# ftdi_rs232_bsl.net
KiCad netlist of a schematic drawn in EAGLE
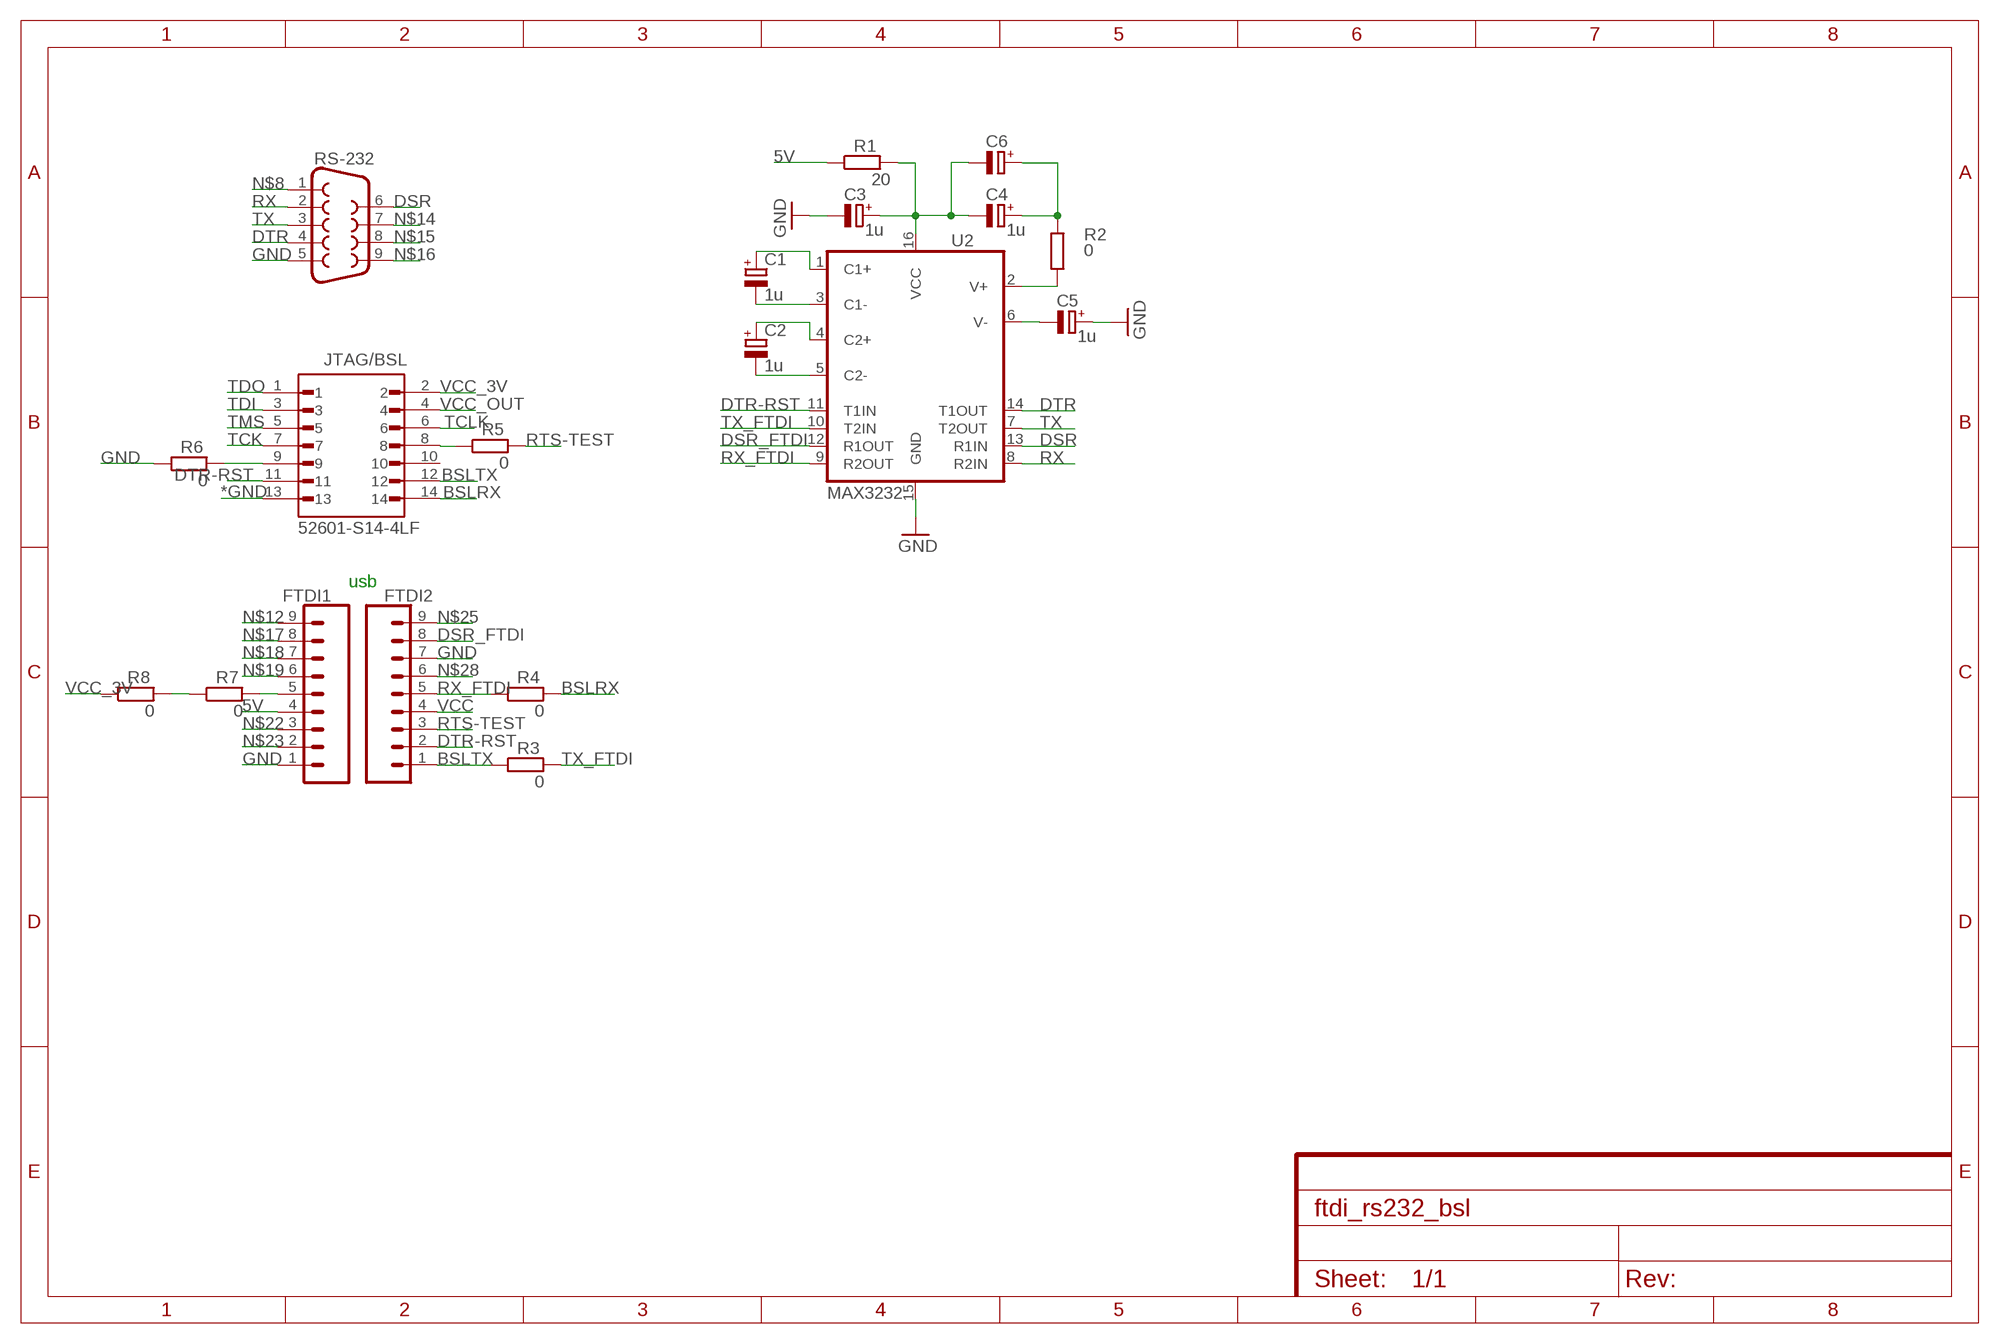
[diagram p0: schematic, sheet 1]

(export (version "E")
  (design (tool "Eeschema 10.0.6"))
  (components
    (comp (ref "C1")
      (value "1u")
      (footprint "eagle-import:B_3528-21W")
      (libsource (lib "eagle-import") (part "CPOL-EUB/3528-21W"))
    )
    (comp (ref "C2")
      (value "1u")
      (footprint "eagle-import:B_3528-21W")
      (libsource (lib "eagle-import") (part "CPOL-EUB/3528-21W"))
    )
    (comp (ref "C3")
      (value "1u")
      (footprint "eagle-import:B_3528-21W")
      (libsource (lib "eagle-import") (part "CPOL-EUB/3528-21W"))
    )
    (comp (ref "C4")
      (value "1u")
      (footprint "eagle-import:B_3528-21W")
      (libsource (lib "eagle-import") (part "CPOL-EUB/3528-21W"))
    )
    (comp (ref "C5")
      (value "1u")
      (footprint "eagle-import:B_3528-21W")
      (libsource (lib "eagle-import") (part "CPOL-EUB/3528-21W"))
    )
    (comp (ref "C6")
      (value "CPOL-EUB/3528-21W")
      (footprint "eagle-import:B_3528-21W")
      (libsource (lib "eagle-import") (part "CPOL-EUB/3528-21W"))
    )
    (comp (ref "FTDI1")
      (value "CONN_09NO_SILK")
      (footprint "eagle-import:1X09_NO_SILK")
      (libsource (lib "eagle-import") (part "CONN_09NO_SILK"))
    )
    (comp (ref "FTDI2")
      (value "CONN_09NO_SILK")
      (footprint "eagle-import:1X09_NO_SILK")
      (libsource (lib "eagle-import") (part "CONN_09NO_SILK"))
    )
    (comp (ref "JTAG/BSL")
      (value "52601-S14-4LF")
      (footprint "eagle-import:AMPHENOL_52601-S14-4LF")
      (fields (field (name "MF") "Amphenol ICC (FCI)"))
      (libsource (lib "eagle-import") (part "52601-S14-4LF"))
    )
    (comp (ref "R1")
      (value "20")
      (footprint "eagle-import:R1206")
      (libsource (lib "eagle-import") (part "R-EU_R1206"))
    )
    (comp (ref "R2")
      (value "0")
      (footprint "eagle-import:R1206")
      (libsource (lib "eagle-import") (part "R-EU_R1206"))
    )
    (comp (ref "R3")
      (value "0")
      (footprint "eagle-import:R1206")
      (libsource (lib "eagle-import") (part "R-EU_R1206"))
    )
    (comp (ref "R4")
      (value "0")
      (footprint "eagle-import:R1206")
      (libsource (lib "eagle-import") (part "R-EU_R1206"))
    )
    (comp (ref "R5")
      (value "0")
      (footprint "eagle-import:R1206")
      (libsource (lib "eagle-import") (part "R-EU_R1206"))
    )
    (comp (ref "R6")
      (value "0")
      (footprint "eagle-import:R1206")
      (libsource (lib "eagle-import") (part "R-EU_R1206"))
    )
    (comp (ref "R7")
      (value "0")
      (footprint "eagle-import:R1206")
      (libsource (lib "eagle-import") (part "R-EU_R1206"))
    )
    (comp (ref "R8")
      (value "0")
      (footprint "eagle-import:R1206")
      (libsource (lib "eagle-import") (part "R-EU_R1206"))
    )
    (comp (ref "RS-232")
      (value "DB9MALE")
      (footprint "eagle-import:DB9_MALE")
      (libsource (lib "eagle-import") (part "DB9MALE"))
    )
    (comp (ref "U2")
      (value "MAX3232")
      (footprint "eagle-import:DIP16")
      (libsource (lib "eagle-import") (part "MAX2323PTH"))
    )
  )
  (nets
    (net (code "1") (name "/*GND") (class "Default")
      (node (ref "JTAG/BSL") (pin "13") (pinfunction "13_13") (pintype "passive"))
    )
    (net (code "2") (name "/5V") (class "Default")
      (node (ref "FTDI1") (pin "4") (pinfunction "4_4") (pintype "passive"))
      (node (ref "R1") (pin "1") (pinfunction "1_1") (pintype "passive"))
    )
    (net (code "3") (name "/BSLRX") (class "Default")
      (node (ref "JTAG/BSL") (pin "14") (pinfunction "14_14") (pintype "passive"))
      (node (ref "R4") (pin "2") (pinfunction "2_2") (pintype "passive"))
    )
    (net (code "4") (name "/BSLTX") (class "Default")
      (node (ref "FTDI2") (pin "1") (pinfunction "1_1") (pintype "passive"))
      (node (ref "JTAG/BSL") (pin "12") (pinfunction "12_12") (pintype "passive"))
      (node (ref "R3") (pin "1") (pinfunction "1_1") (pintype "passive"))
    )
    (net (code "5") (name "/DSR") (class "Default")
      (node (ref "RS-232") (pin "6") (pinfunction "6_6") (pintype "passive"))
      (node (ref "U2") (pin "13") (pinfunction "R1IN_13") (pintype "input"))
    )
    (net (code "6") (name "/DSR_FTDI") (class "Default")
      (node (ref "FTDI2") (pin "8") (pinfunction "8_8") (pintype "passive"))
      (node (ref "U2") (pin "12") (pinfunction "R1OUT_12") (pintype "output"))
    )
    (net (code "7") (name "/DTR") (class "Default")
      (node (ref "RS-232") (pin "4") (pinfunction "4_4") (pintype "passive"))
      (node (ref "U2") (pin "14") (pinfunction "T1OUT_14") (pintype "output"))
    )
    (net (code "8") (name "/DTR-RST") (class "Default")
      (node (ref "FTDI2") (pin "2") (pinfunction "2_2") (pintype "passive"))
      (node (ref "JTAG/BSL") (pin "11") (pinfunction "11_11") (pintype "passive"))
      (node (ref "U2") (pin "11") (pinfunction "T1IN_11") (pintype "input"))
    )
    (net (code "9") (name "/N$8") (class "Default")
      (node (ref "RS-232") (pin "1") (pinfunction "1_1") (pintype "passive"))
    )
    (net (code "10") (name "/N$12") (class "Default")
      (node (ref "FTDI1") (pin "9") (pinfunction "9_9") (pintype "passive"))
    )
    (net (code "11") (name "/N$14") (class "Default")
      (node (ref "RS-232") (pin "7") (pinfunction "7_7") (pintype "passive"))
    )
    (net (code "12") (name "/N$15") (class "Default")
      (node (ref "RS-232") (pin "8") (pinfunction "8_8") (pintype "passive"))
    )
    (net (code "13") (name "/N$16") (class "Default")
      (node (ref "RS-232") (pin "9") (pinfunction "9_9") (pintype "passive"))
    )
    (net (code "14") (name "/N$17") (class "Default")
      (node (ref "FTDI1") (pin "8") (pinfunction "8_8") (pintype "passive"))
    )
    (net (code "15") (name "/N$18") (class "Default")
      (node (ref "FTDI1") (pin "7") (pinfunction "7_7") (pintype "passive"))
    )
    (net (code "16") (name "/N$19") (class "Default")
      (node (ref "FTDI1") (pin "6") (pinfunction "6_6") (pintype "passive"))
    )
    (net (code "17") (name "/N$22") (class "Default")
      (node (ref "FTDI1") (pin "3") (pinfunction "3_3") (pintype "passive"))
    )
    (net (code "18") (name "/N$23") (class "Default")
      (node (ref "FTDI1") (pin "2") (pinfunction "2_2") (pintype "passive"))
    )
    (net (code "19") (name "/N$25") (class "Default")
      (node (ref "FTDI2") (pin "9") (pinfunction "9_9") (pintype "passive"))
    )
    (net (code "20") (name "/N$28") (class "Default")
      (node (ref "FTDI2") (pin "6") (pinfunction "6_6") (pintype "passive"))
    )
    (net (code "21") (name "/RTS-TEST") (class "Default")
      (node (ref "FTDI2") (pin "3") (pinfunction "3_3") (pintype "passive"))
      (node (ref "R5") (pin "2") (pinfunction "2_2") (pintype "passive"))
    )
    (net (code "22") (name "/RX") (class "Default")
      (node (ref "RS-232") (pin "2") (pinfunction "2_2") (pintype "passive"))
      (node (ref "U2") (pin "8") (pinfunction "R2IN_8") (pintype "input"))
    )
    (net (code "23") (name "/RX_FTDI") (class "Default")
      (node (ref "FTDI2") (pin "5") (pinfunction "5_5") (pintype "passive"))
      (node (ref "R4") (pin "1") (pinfunction "1_1") (pintype "passive"))
      (node (ref "U2") (pin "9") (pinfunction "R2OUT_9") (pintype "output"))
    )
    (net (code "24") (name "/TCK") (class "Default")
      (node (ref "JTAG/BSL") (pin "7") (pinfunction "7_7") (pintype "passive"))
    )
    (net (code "25") (name "/TCLK") (class "Default")
      (node (ref "JTAG/BSL") (pin "6") (pinfunction "6_6") (pintype "passive"))
    )
    (net (code "26") (name "/TDI") (class "Default")
      (node (ref "JTAG/BSL") (pin "3") (pinfunction "3_3") (pintype "passive"))
    )
    (net (code "27") (name "/TDO") (class "Default")
      (node (ref "JTAG/BSL") (pin "1") (pinfunction "1_1") (pintype "passive"))
    )
    (net (code "28") (name "/TMS") (class "Default")
      (node (ref "JTAG/BSL") (pin "5") (pinfunction "5_5") (pintype "passive"))
    )
    (net (code "29") (name "/TX") (class "Default")
      (node (ref "RS-232") (pin "3") (pinfunction "3_3") (pintype "passive"))
      (node (ref "U2") (pin "7") (pinfunction "T2OUT_7") (pintype "output"))
    )
    (net (code "30") (name "/TX_FTDI") (class "Default")
      (node (ref "R3") (pin "2") (pinfunction "2_2") (pintype "passive"))
      (node (ref "U2") (pin "10") (pinfunction "T2IN_10") (pintype "input"))
    )
    (net (code "31") (name "/VCC") (class "Default")
      (node (ref "FTDI2") (pin "4") (pinfunction "4_4") (pintype "passive"))
    )
    (net (code "32") (name "/VCC_3V") (class "Default")
      (node (ref "JTAG/BSL") (pin "2") (pinfunction "2_2") (pintype "passive"))
      (node (ref "R8") (pin "1") (pinfunction "1_1") (pintype "passive"))
    )
    (net (code "33") (name "/VCC_OUT") (class "Default")
      (node (ref "JTAG/BSL") (pin "4") (pinfunction "4_4") (pintype "passive"))
    )
    (net (code "34") (name "GND") (class "Default")
      (node (ref "C3") (pin "-") (pinfunction "-_-") (pintype "passive"))
      (node (ref "C5") (pin "+") (pinfunction "+_+") (pintype "passive"))
      (node (ref "FTDI1") (pin "1") (pinfunction "1_1") (pintype "passive"))
      (node (ref "FTDI2") (pin "7") (pinfunction "7_7") (pintype "passive"))
      (node (ref "R6") (pin "1") (pinfunction "1_1") (pintype "passive"))
      (node (ref "RS-232") (pin "5") (pinfunction "5_5") (pintype "passive"))
      (node (ref "U2") (pin "15") (pinfunction "GND_15") (pintype "bidirectional"))
    )
    (net (code "35") (name "Net-(C4-Pad+)") (class "Default")
      (node (ref "C4") (pin "+") (pinfunction "+_+") (pintype "passive"))
      (node (ref "C6") (pin "+") (pinfunction "+_+") (pintype "passive"))
      (node (ref "R2") (pin "2") (pinfunction "2_2") (pintype "passive"))
    )
    (net (code "36") (name "Net-(FTDI1-Pad5)") (class "Default")
      (node (ref "FTDI1") (pin "5") (pinfunction "5_5") (pintype "passive"))
      (node (ref "R7") (pin "2") (pinfunction "2_2") (pintype "passive"))
    )
    (net (code "37") (name "Net-(JTAG/BSL-Pad8)") (class "Default")
      (node (ref "JTAG/BSL") (pin "8") (pinfunction "8_8") (pintype "passive"))
      (node (ref "R5") (pin "1") (pinfunction "1_1") (pintype "passive"))
    )
    (net (code "38") (name "Net-(JTAG/BSL-Pad9)") (class "Default")
      (node (ref "JTAG/BSL") (pin "9") (pinfunction "9_9") (pintype "passive"))
      (node (ref "R6") (pin "2") (pinfunction "2_2") (pintype "passive"))
    )
    (net (code "39") (name "Net-(R7-Pad1)") (class "Default")
      (node (ref "R7") (pin "1") (pinfunction "1_1") (pintype "passive"))
      (node (ref "R8") (pin "2") (pinfunction "2_2") (pintype "passive"))
    )
    (net (code "40") (name "Net-(U2-C1+)") (class "Default")
      (node (ref "C1") (pin "+") (pinfunction "+_+") (pintype "passive"))
      (node (ref "U2") (pin "1") (pinfunction "C1+_1") (pintype "bidirectional"))
    )
    (net (code "41") (name "Net-(U2-C1-)") (class "Default")
      (node (ref "C1") (pin "-") (pinfunction "-_-") (pintype "passive"))
      (node (ref "U2") (pin "3") (pinfunction "C1-_3") (pintype "bidirectional"))
    )
    (net (code "42") (name "Net-(U2-C2+)") (class "Default")
      (node (ref "C2") (pin "+") (pinfunction "+_+") (pintype "passive"))
      (node (ref "U2") (pin "4") (pinfunction "C2+_4") (pintype "bidirectional"))
    )
    (net (code "43") (name "Net-(U2-C2-)") (class "Default")
      (node (ref "C2") (pin "-") (pinfunction "-_-") (pintype "passive"))
      (node (ref "U2") (pin "5") (pinfunction "C2-_5") (pintype "bidirectional"))
    )
    (net (code "44") (name "Net-(U2-V+)") (class "Default")
      (node (ref "R2") (pin "1") (pinfunction "1_1") (pintype "passive"))
      (node (ref "U2") (pin "2") (pinfunction "V+_2") (pintype "bidirectional"))
    )
    (net (code "45") (name "Net-(U2-V-)") (class "Default")
      (node (ref "C5") (pin "-") (pinfunction "-_-") (pintype "passive"))
      (node (ref "U2") (pin "6") (pinfunction "V-_6") (pintype "bidirectional"))
    )
    (net (code "46") (name "Net-(U2-VCC)") (class "Default")
      (node (ref "C3") (pin "+") (pinfunction "+_+") (pintype "passive"))
      (node (ref "C4") (pin "-") (pinfunction "-_-") (pintype "passive"))
      (node (ref "C6") (pin "-") (pinfunction "-_-") (pintype "passive"))
      (node (ref "R1") (pin "2") (pinfunction "2_2") (pintype "passive"))
      (node (ref "U2") (pin "16") (pinfunction "VCC_16") (pintype "bidirectional"))
    )
    (net (code "47") (name "unconnected-(JTAG/BSL-Pad10)") (class "Default")
      (node (ref "JTAG/BSL") (pin "10") (pinfunction "10_10") (pintype "passive"))
    )
  )
)
